# band.net
KiCad netlist of a schematic drawn in Altium Designer
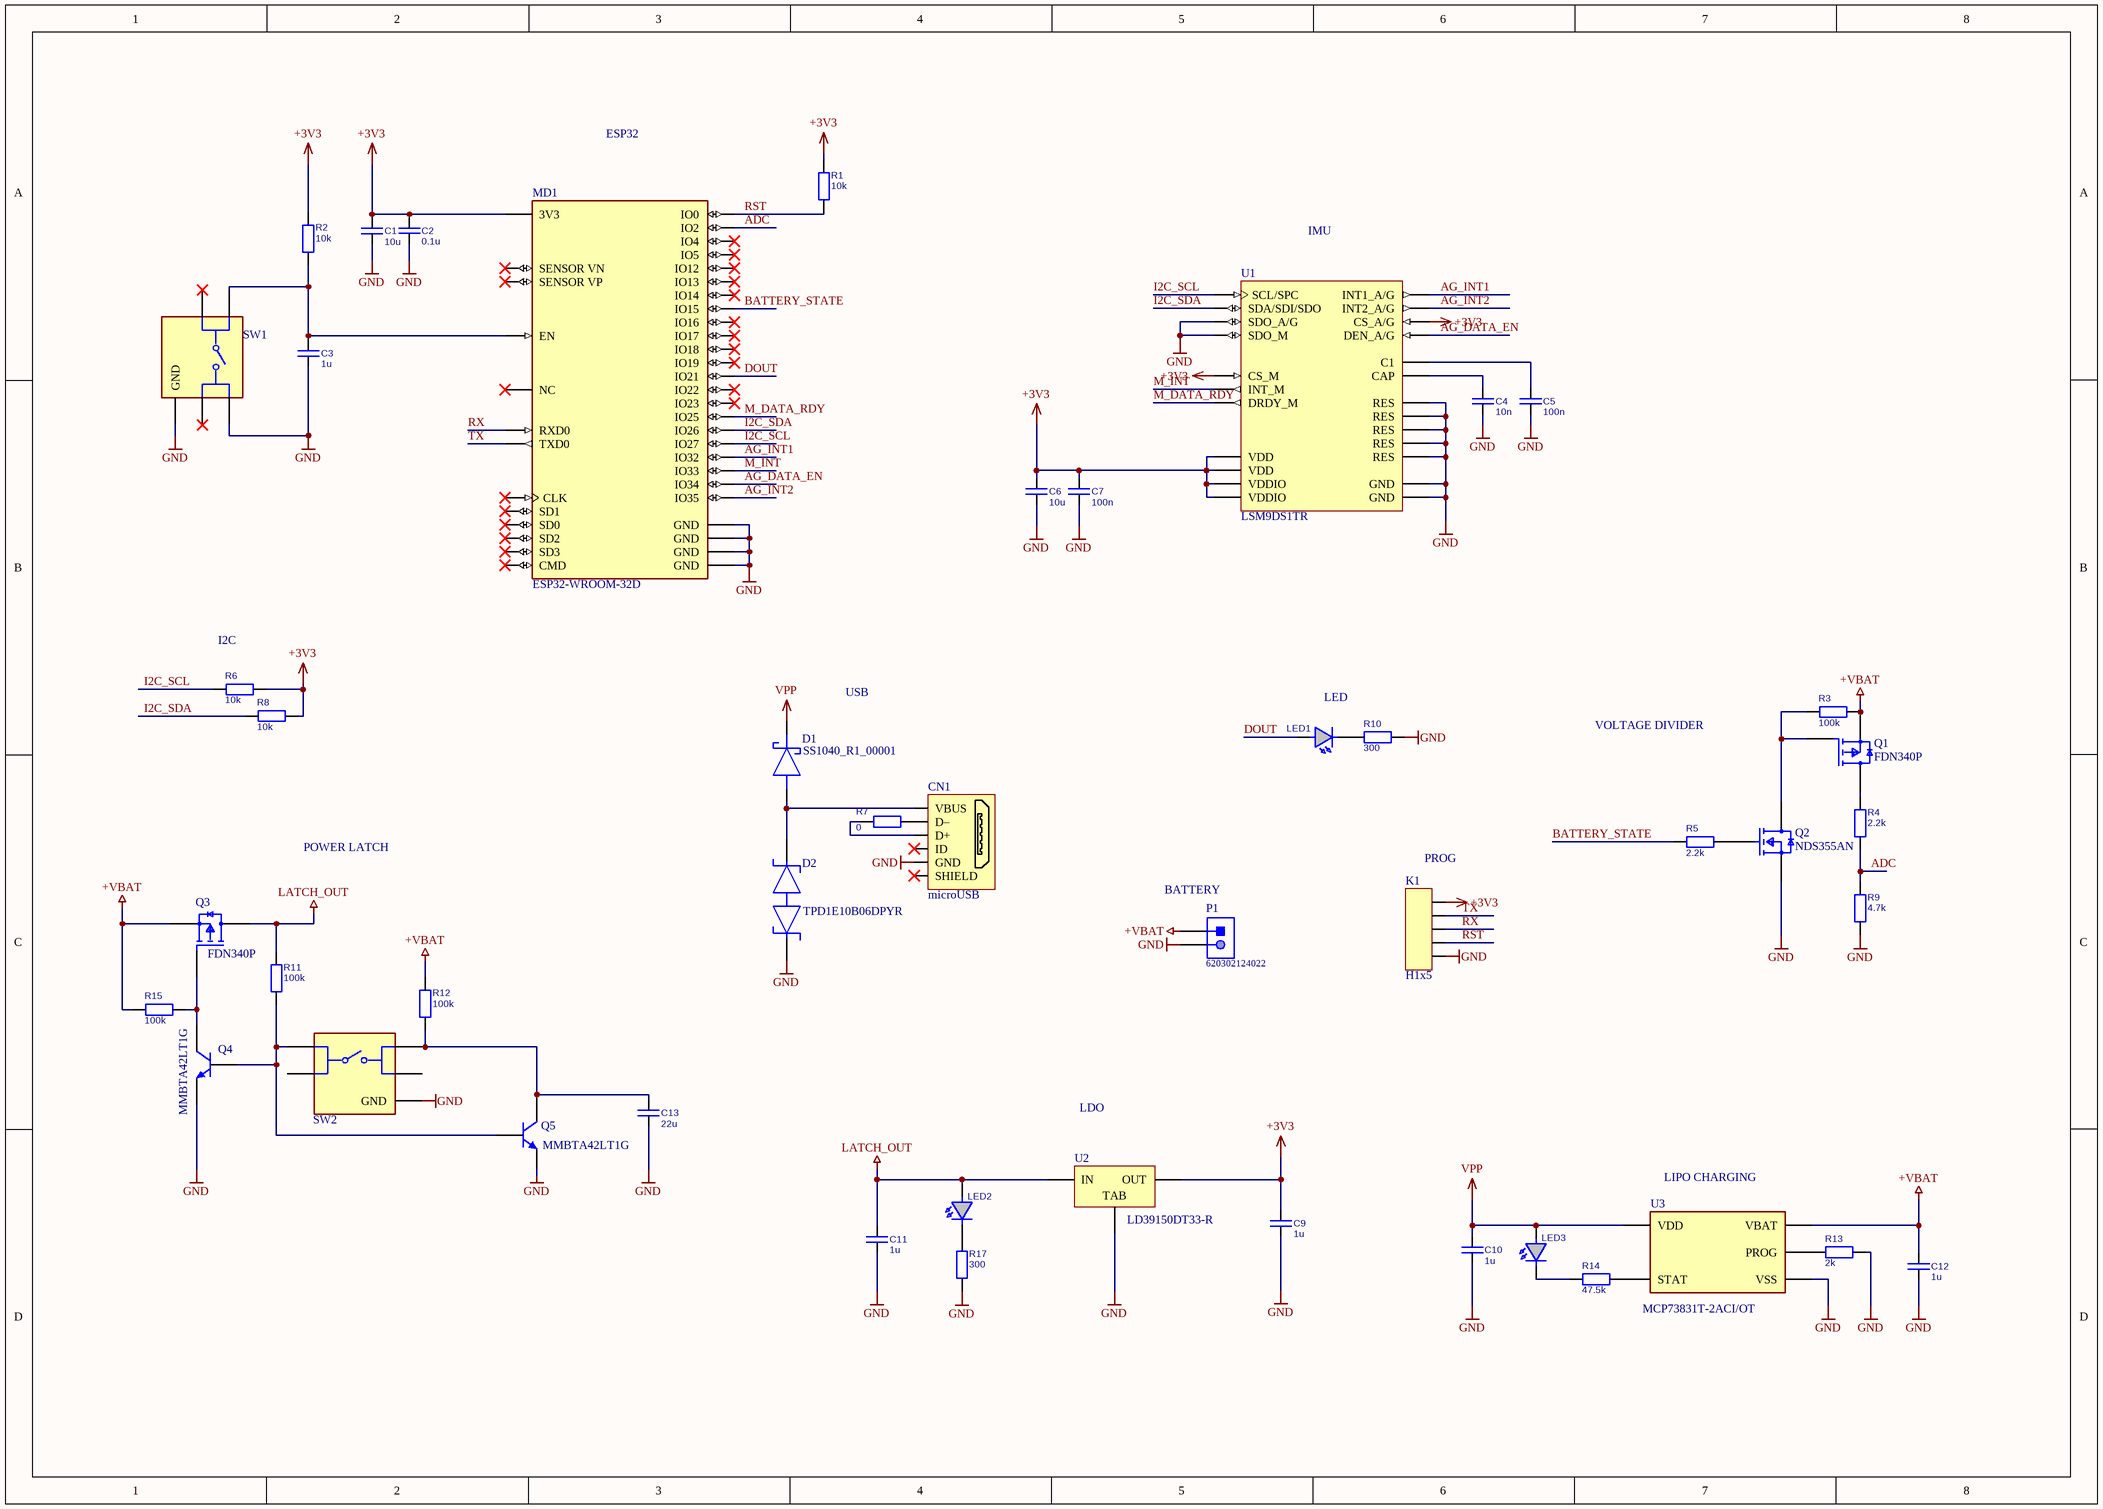
[diagram p0: band.SchDoc]

(export (version "E")
  (design (tool "Eeschema 10.0.6"))
  (components
    (comp (ref "C1")
      (value "10u")
      (footprint "C0805")
      (description "Capacitor")
      (libsource (lib "General") (part "C"))
    )
    (comp (ref "C2")
      (value "0.1u")
      (footprint "C0805")
      (description "Capacitor")
      (libsource (lib "General") (part "C"))
    )
    (comp (ref "C3")
      (value "1u")
      (footprint "C0805")
      (description "Capacitor")
      (libsource (lib "General") (part "C"))
    )
    (comp (ref "C4")
      (value "10n")
      (footprint "C0805")
      (description "Capacitor")
      (libsource (lib "General") (part "C"))
    )
    (comp (ref "C5")
      (value "100n")
      (footprint "C0805")
      (description "Capacitor")
      (libsource (lib "General") (part "C"))
    )
    (comp (ref "C6")
      (value "10u")
      (footprint "C0805")
      (description "Capacitor")
      (libsource (lib "General") (part "C"))
    )
    (comp (ref "C7")
      (value "100n")
      (footprint "C0805")
      (description "Capacitor")
      (libsource (lib "General") (part "C"))
    )
    (comp (ref "C9")
      (value "1u")
      (footprint "C0805")
      (description "Capacitor")
      (libsource (lib "General") (part "C"))
    )
    (comp (ref "C10")
      (value "1u")
      (footprint "C0805")
      (description "Capacitor")
      (libsource (lib "General") (part "C"))
    )
    (comp (ref "C11")
      (value "1u")
      (footprint "C0805")
      (description "Capacitor")
      (libsource (lib "General") (part "C"))
    )
    (comp (ref "C12")
      (value "1u")
      (footprint "C0805")
      (description "Capacitor")
      (libsource (lib "General") (part "C"))
    )
    (comp (ref "C13")
      (value "22u")
      (footprint "C0805")
      (description "Capacitor")
      (libsource (lib "General") (part "C"))
    )
    (comp (ref "CN1")
      (value "microUSB")
      (footprint "micro-USB-HRS-ZX62D-B-5PA8")
      (description "micro USB-B socket (HIROSE ZX62D-B-5PA8)")
      (libsource (lib "Kon_Tipk") (part "microUSB-B-socket (HIROSE ZX62D-B-5PA8)"))
    )
    (comp (ref "D1")
      (value "SS1040_R1_00001")
      (footprint "SamacSys:SS1040_R1_00001")
      (description "Schottky Diode")
      (libsource (lib "band") (part "SS1040_R1_00001"))
    )
    (comp (ref "D2")
      (value "TPD1E10B06DPYR")
      (footprint "FP-DPY0002A-MFG")
      (description "TVS DIODE 5.5V 14V 2X1SON")
      (libsource (lib "Altium Content Vault") (part "208e19b57522434895fa003e5d5b197"))
    )
    (comp (ref "K1")
      (value "H1x5")
      (footprint "H1x5")
      (description "Header 1x5 (male)")
      (libsource (lib "Kon_Tipk") (part "H1x5"))
    )
    (comp (ref "LED1") (value "LED") (footprint "LED0805G") (libsource (lib "Displays") (part "LED")))
    (comp (ref "LED2") (value "LED") (footprint "LED0805G") (libsource (lib "Displays") (part "LED")))
    (comp (ref "LED3") (value "LED") (footprint "LED0805G") (libsource (lib "Displays") (part "LED")))
    (comp (ref "MD1")
      (value "ESP32-WROOM-32D")
      (footprint "FP-ESP32-WROOM-32D-MFG")
      (description "WIFI MODULE 32MBITS SPI FLASH")
      (fields
        (field (name "OCTOPART") "https://octopart.com/esp32-wroom-32d-espressif+systems-91040050")
        (field (name "MANUFACTURER") "Espressif Systems")
      )
      (libsource (lib "Altium Content Vault") (part "a031a76f8c27026a7a7f4657ff233a3"))
    )
    (comp (ref "P1")
      (value "620302124022")
      (footprint "620302124022")
      (description "Male Shrouded Header WR-WTB, SMT, Vertical, pitch 2 mm, 1 x 2 position")
      (fields (field (name "MANUFACTURER") "Wurth Elektronik") (field (name "PUBLISHER") "WurthElektronik"))
      (libsource (lib "Altium Content Vault") (part "WE-CN-1P-M-R2"))
    )
    (comp (ref "Q1")
      (value "FDN340P")
      (footprint "FP-527AG-MFG")
      (description "MOSFET P-CH 20V 2A SSOT3")
      (libsource (lib "Altium Content Vault") (part "d23f43cc42f60b967b7caccf14518fd"))
    )
    (comp (ref "Q2")
      (value "NDS355AN")
      (footprint "FP-527AG-01-IPC_C")
      (description "MOSFET N-CH 30V 1.7A SSOT3")
      (fields
        (field (name "OCTOPART") "https://octopart.com/nds355an-on+semiconductor-84330922")
        (field (name "MANUFACTURER") "ON Semiconductor")
      )
      (libsource (lib "Altium Content Vault") (part "3b9c635fedb024a5347a57b145af9cc"))
    )
    (comp (ref "Q3")
      (value "FDN340P")
      (footprint "FP-527AG-MFG")
      (description "MOSFET P-CH 20V 2A SSOT3")
      (libsource (lib "Altium Content Vault") (part "d23f43cc42f60b967b7caccf14518fd"))
    )
    (comp (ref "Q4")
      (value "MMBTA42LT1G")
      (footprint "ONSC-SOT-23-3-318-08_V")
      (description "High Voltage Transistor, NPN Silicon, 3-Pin SOT-23, Pb-Free, Tape and Reel")
      (fields (field (name "MANUFACTURER") "On Semiconductor"))
      (libsource (lib "Altium Content Vault") (part "ONSC-NPN-B1E2C3-3"))
    )
    (comp (ref "Q5")
      (value "MMBTA42LT1G")
      (footprint "ONSC-SOT-23-3-318-08_V")
      (description "High Voltage Transistor, NPN Silicon, 3-Pin SOT-23, Pb-Free, Tape and Reel")
      (fields (field (name "MANUFACTURER") "On Semiconductor"))
      (libsource (lib "Altium Content Vault") (part "ONSC-NPN-B1E2C3-3"))
    )
    (comp (ref "R1")
      (value "10k")
      (footprint "R0805")
      (description "R")
      (libsource (lib "General") (part "R"))
    )
    (comp (ref "R2")
      (value "10k")
      (footprint "R0805")
      (description "R")
      (libsource (lib "General") (part "R"))
    )
    (comp (ref "R3")
      (value "100k")
      (footprint "R0805")
      (description "R")
      (libsource (lib "General") (part "R"))
    )
    (comp (ref "R4")
      (value "2.2k")
      (footprint "R0805")
      (description "R")
      (libsource (lib "General") (part "R"))
    )
    (comp (ref "R5")
      (value "2.2k")
      (footprint "R0805")
      (description "R")
      (libsource (lib "General") (part "R"))
    )
    (comp (ref "R6")
      (value "10k")
      (footprint "R0805")
      (description "R")
      (libsource (lib "General") (part "R"))
    )
    (comp (ref "R7") (value "0") (footprint "R0805") (description "R") (libsource (lib "General") (part "R")))
    (comp (ref "R8")
      (value "10k")
      (footprint "R0805")
      (description "R")
      (libsource (lib "General") (part "R"))
    )
    (comp (ref "R9")
      (value "4.7k")
      (footprint "R0805")
      (description "R")
      (libsource (lib "General") (part "R"))
    )
    (comp (ref "R10")
      (value "300")
      (footprint "R0805")
      (description "R")
      (libsource (lib "General") (part "R"))
    )
    (comp (ref "R11")
      (value "100k")
      (footprint "R0805")
      (description "R")
      (libsource (lib "General") (part "R"))
    )
    (comp (ref "R12")
      (value "100k")
      (footprint "R0805")
      (description "R")
      (libsource (lib "General") (part "R"))
    )
    (comp (ref "R13")
      (value "2k")
      (footprint "R0805")
      (description "R")
      (libsource (lib "General") (part "R"))
    )
    (comp (ref "R14")
      (value "47.5k")
      (footprint "R0805")
      (description "R")
      (libsource (lib "General") (part "R"))
    )
    (comp (ref "R15")
      (value "100k")
      (footprint "R0805")
      (description "R")
      (libsource (lib "General") (part "R"))
    )
    (comp (ref "R17")
      (value "300")
      (footprint "R0805")
      (description "R")
      (libsource (lib "General") (part "R"))
    )
    (comp (ref "SW1")
      (value "FSM1LP")
      (footprint "FP-FSM1LP-MFG")
      (description "SWITCH TACTILE SPST-NO 0.05A 24V")
      (libsource (lib "") (part "CMP-03402-000015-1_1"))
    )
    (comp (ref "SW2")
      (value "FSM1LP")
      (footprint "FP-FSM1LP-MFG")
      (description "SWITCH TACTILE SPST-NO 0.05A 24V")
      (libsource (lib "band") (part "CMP-03402-000015-1"))
    )
    (comp (ref "U1")
      (value "LSM9DS1TR")
      (footprint "STM-LGA-24_3500X3000X1000")
      (fields (field (name "PARTNUMBER") "LSM9DS1") (field (name "MANUFACTURER") "STMicroelectronics"))
      (libsource (lib "Altium Content Vault") (part "STM-LSM9DS1-24"))
    )
    (comp (ref "U2")
      (value "LD39150DT33-R")
      (footprint "TO-252_M")
      (description "Ultra Low Drop BICMOS Voltage Regulator, 3.3V, 3-Pin DPAK, Tape and Reel")
      (libsource (lib "Altium Content Vault") (part "PM-REG-LD29150-SOT3"))
    )
    (comp (ref "U3")
      (value "MCP73831T-2ACI/OT")
      (footprint "FP-C04-091-OT-IPC_B")
      (description "IC CONTROLLR LI-ION 4.2V SOT23-5")
      (libsource (lib "Altium Content Vault") (part "61f5a3bb3429d9e0caadea342aa3b19"))
    )
  )
  (nets
    (net (code "1") (name "+3V3") (class "Default")
      (node (ref "C1") (pin "1") (pinfunction "1_1") (pintype "passive"))
      (node (ref "C2") (pin "1") (pinfunction "1_1") (pintype "passive"))
      (node (ref "C6") (pin "1") (pinfunction "1_1") (pintype "passive"))
      (node (ref "C7") (pin "1") (pinfunction "1_1") (pintype "passive"))
      (node (ref "C9") (pin "1") (pinfunction "1_1") (pintype "passive"))
      (node (ref "K1") (pin "1") (pinfunction "1_1") (pintype "passive"))
      (node (ref "MD1") (pin "2") (pinfunction "3V3_2") (pintype "power_in"))
      (node (ref "R1") (pin "1") (pintype "passive"))
      (node (ref "R2") (pin "2") (pintype "passive"))
      (node (ref "R6") (pin "2") (pintype "passive"))
      (node (ref "R8") (pin "2") (pintype "passive"))
      (node (ref "U1") (pin "1") (pinfunction "VDDIO_1") (pintype "power_in"))
      (node (ref "U1") (pin "22") (pinfunction "VDD_22") (pintype "power_in"))
      (node (ref "U1") (pin "23") (pinfunction "VDD_23") (pintype "power_in"))
      (node (ref "U1") (pin "3") (pinfunction "VDDIO_3") (pintype "power_in"))
      (node (ref "U1") (pin "7") (pinfunction "CS_A/G_7") (pintype "input"))
      (node (ref "U1") (pin "8") (pinfunction "CS_M_8") (pintype "input"))
      (node (ref "U2") (pin "3") (pinfunction "OUT_3") (pintype "power_in"))
    )
    (net (code "2") (name "+VBAT") (class "Default")
      (node (ref "C12") (pin "1") (pinfunction "1_1") (pintype "passive"))
      (node (ref "P1") (pin "1") (pinfunction "1_1") (pintype "passive"))
      (node (ref "Q1") (pin "2") (pinfunction "S_2") (pintype "passive"))
      (node (ref "Q3") (pin "2") (pinfunction "S_2") (pintype "passive"))
      (node (ref "R12") (pin "2") (pintype "passive"))
      (node (ref "R15") (pin "2") (pintype "passive"))
      (node (ref "R3") (pin "1") (pintype "passive"))
      (node (ref "U3") (pin "3") (pinfunction "VBAT_3") (pintype "power_in"))
    )
    (net (code "3") (name "/ADC") (class "Default")
      (node (ref "MD1") (pin "24") (pinfunction "IO2_24") (pintype "bidirectional"))
      (node (ref "R4") (pin "2") (pintype "passive"))
      (node (ref "R9") (pin "2") (pintype "passive"))
    )
    (net (code "4") (name "/AG_DATA_EN") (class "Default")
      (node (ref "MD1") (pin "6") (pinfunction "IO34_6") (pintype "bidirectional"))
      (node (ref "U1") (pin "13") (pinfunction "DEN_A/G_13") (pintype "input"))
    )
    (net (code "5") (name "/AG_INT1") (class "Default")
      (node (ref "MD1") (pin "8") (pinfunction "IO32_8") (pintype "bidirectional"))
      (node (ref "U1") (pin "11") (pinfunction "INT1_A/G_11") (pintype "output"))
    )
    (net (code "6") (name "/AG_INT2") (class "Default")
      (node (ref "MD1") (pin "7") (pinfunction "IO35_7") (pintype "bidirectional"))
      (node (ref "U1") (pin "12") (pinfunction "INT2_A/G_12") (pintype "output"))
    )
    (net (code "7") (name "/BATTERY_STATE") (class "Default")
      (node (ref "MD1") (pin "23") (pinfunction "IO15_23") (pintype "bidirectional"))
      (node (ref "R5") (pin "1") (pintype "passive"))
    )
    (net (code "8") (name "/DOUT") (class "Default")
      (node (ref "LED1") (pin "A") (pinfunction "1_A") (pintype "passive"))
      (node (ref "MD1") (pin "33") (pinfunction "IO21_33") (pintype "bidirectional"))
    )
    (net (code "9") (name "/I2C_SCL") (class "Default")
      (node (ref "MD1") (pin "12") (pinfunction "IO27_12") (pintype "bidirectional"))
      (node (ref "R6") (pin "1") (pintype "passive"))
      (node (ref "U1") (pin "2") (pinfunction "SCL/SPC_2") (pintype "input"))
    )
    (net (code "10") (name "/I2C_SDA") (class "Default")
      (node (ref "MD1") (pin "11") (pinfunction "IO26_11") (pintype "bidirectional"))
      (node (ref "R8") (pin "1") (pintype "passive"))
      (node (ref "U1") (pin "4") (pinfunction "SDA/SDI/SDO_4") (pintype "bidirectional"))
    )
    (net (code "11") (name "/M_DATA_RDY") (class "Default")
      (node (ref "MD1") (pin "10") (pinfunction "IO25_10") (pintype "bidirectional"))
      (node (ref "U1") (pin "9") (pinfunction "DRDY_M_9") (pintype "output"))
    )
    (net (code "12") (name "/M_INT") (class "Default")
      (node (ref "MD1") (pin "9") (pinfunction "IO33_9") (pintype "bidirectional"))
      (node (ref "U1") (pin "10") (pinfunction "INT_M_10") (pintype "output"))
    )
    (net (code "13") (name "/RST") (class "Default")
      (node (ref "K1") (pin "4") (pinfunction "4_4") (pintype "passive"))
      (node (ref "MD1") (pin "25") (pinfunction "IO0_25") (pintype "bidirectional"))
      (node (ref "R1") (pin "2") (pintype "passive"))
    )
    (net (code "14") (name "/RX") (class "Default")
      (node (ref "K1") (pin "3") (pinfunction "3_3") (pintype "passive"))
      (node (ref "MD1") (pin "34") (pinfunction "RXD0_34") (pintype "input"))
    )
    (net (code "15") (name "/TX") (class "Default")
      (node (ref "K1") (pin "2") (pinfunction "2_2") (pintype "passive"))
      (node (ref "MD1") (pin "35") (pinfunction "TXD0_35") (pintype "output"))
    )
    (net (code "16") (name "GND") (class "Default")
      (node (ref "C1") (pin "2") (pinfunction "2_2") (pintype "passive"))
      (node (ref "C10") (pin "2") (pinfunction "2_2") (pintype "passive"))
      (node (ref "C11") (pin "1") (pinfunction "1_1") (pintype "passive"))
      (node (ref "C12") (pin "2") (pinfunction "2_2") (pintype "passive"))
      (node (ref "C13") (pin "1") (pinfunction "1_1") (pintype "passive"))
      (node (ref "C2") (pin "2") (pinfunction "2_2") (pintype "passive"))
      (node (ref "C3") (pin "2") (pinfunction "2_2") (pintype "passive"))
      (node (ref "C4") (pin "2") (pinfunction "2_2") (pintype "passive"))
      (node (ref "C5") (pin "2") (pinfunction "2_2") (pintype "passive"))
      (node (ref "C6") (pin "2") (pinfunction "2_2") (pintype "passive"))
      (node (ref "C7") (pin "2") (pinfunction "2_2") (pintype "passive"))
      (node (ref "C9") (pin "2") (pinfunction "2_2") (pintype "passive"))
      (node (ref "CN1") (pin "5") (pinfunction "GND_5") (pintype "passive"))
      (node (ref "D2") (pin "1") (pinfunction "1_1") (pintype "passive"))
      (node (ref "K1") (pin "5") (pinfunction "5_5") (pintype "passive"))
      (node (ref "MD1") (pin "1") (pinfunction "GND_1") (pintype "power_in"))
      (node (ref "MD1") (pin "15") (pinfunction "GND_15") (pintype "power_in"))
      (node (ref "MD1") (pin "38") (pinfunction "GND_38") (pintype "power_in"))
      (node (ref "MD1") (pin "39") (pinfunction "GND_39") (pintype "power_in"))
      (node (ref "P1") (pin "2") (pinfunction "2_2") (pintype "passive"))
      (node (ref "Q2") (pin "2") (pinfunction "S_2") (pintype "passive"))
      (node (ref "Q4") (pin "2") (pinfunction "E_2") (pintype "passive"))
      (node (ref "Q5") (pin "2") (pinfunction "E_2") (pintype "passive"))
      (node (ref "R10") (pin "2") (pintype "passive"))
      (node (ref "R13") (pin "1") (pintype "passive"))
      (node (ref "R17") (pin "1") (pintype "passive"))
      (node (ref "R9") (pin "1") (pintype "passive"))
      (node (ref "SW1") (pin "3") (pinfunction "3_3") (pintype "passive"))
      (node (ref "SW1") (pin "5") (pinfunction "GND_5") (pintype "power_in"))
      (node (ref "SW2") (pin "5") (pinfunction "GND_5") (pintype "power_in"))
      (node (ref "U1") (pin "14") (pinfunction "RES_14") (pintype "passive"))
      (node (ref "U1") (pin "15") (pinfunction "RES_15") (pintype "passive"))
      (node (ref "U1") (pin "16") (pinfunction "RES_16") (pintype "passive"))
      (node (ref "U1") (pin "17") (pinfunction "RES_17") (pintype "passive"))
      (node (ref "U1") (pin "18") (pinfunction "RES_18") (pintype "passive"))
      (node (ref "U1") (pin "19") (pinfunction "GND_19") (pintype "power_in"))
      (node (ref "U1") (pin "20") (pinfunction "GND_20") (pintype "power_in"))
      (node (ref "U1") (pin "5") (pinfunction "SDO_A/G_5") (pintype "bidirectional"))
      (node (ref "U1") (pin "6") (pinfunction "SDO_M_6") (pintype "bidirectional"))
      (node (ref "U2") (pin "4") (pinfunction "TAB_4") (pintype "passive"))
      (node (ref "U3") (pin "2") (pinfunction "VSS_2") (pintype "power_in"))
    )
    (net (code "17") (name "LATCH_OUT") (class "Default")
      (node (ref "C11") (pin "2") (pinfunction "2_2") (pintype "passive"))
      (node (ref "LED2") (pin "A") (pinfunction "1_A") (pintype "passive"))
      (node (ref "Q3") (pin "3") (pinfunction "D_3") (pintype "passive"))
      (node (ref "R11") (pin "2") (pintype "passive"))
      (node (ref "U2") (pin "1") (pinfunction "IN_1") (pintype "power_in"))
    )
    (net (code "18") (name "Net-(CN1-D+)") (class "Default")
      (node (ref "CN1") (pin "3") (pinfunction "D+_3") (pintype "passive"))
      (node (ref "R7") (pin "2") (pintype "passive"))
    )
    (net (code "19") (name "Net-(CN1-D–)") (class "Default")
      (node (ref "CN1") (pin "2") (pinfunction "D–_2") (pintype "passive"))
      (node (ref "R7") (pin "1") (pintype "passive"))
    )
    (net (code "20") (name "Net-(CN1-VBUS)") (class "Default")
      (node (ref "CN1") (pin "1") (pinfunction "VBUS_1") (pintype "passive"))
      (node (ref "D1") (pin "2") (pinfunction "A_2") (pintype "passive"))
      (node (ref "D2") (pin "2") (pinfunction "2_2") (pintype "passive"))
    )
    (net (code "21") (name "Net-(LED1-2)") (class "Default")
      (node (ref "LED1") (pin "K") (pinfunction "2_K") (pintype "passive"))
      (node (ref "R10") (pin "1") (pintype "passive"))
    )
    (net (code "22") (name "Net-(LED2-2)") (class "Default")
      (node (ref "LED2") (pin "K") (pinfunction "2_K") (pintype "passive"))
      (node (ref "R17") (pin "2") (pintype "passive"))
    )
    (net (code "23") (name "Net-(LED3-2)") (class "Default")
      (node (ref "LED3") (pin "K") (pinfunction "2_K") (pintype "passive"))
      (node (ref "R14") (pin "2") (pintype "passive"))
    )
    (net (code "24") (name "Net-(MD1-EN)") (class "Default")
      (node (ref "C3") (pin "1") (pinfunction "1_1") (pintype "passive"))
      (node (ref "MD1") (pin "3") (pinfunction "EN_3") (pintype "input"))
      (node (ref "R2") (pin "1") (pintype "passive"))
      (node (ref "SW1") (pin "1") (pinfunction "1_1") (pintype "passive"))
    )
    (net (code "25") (name "Net-(Q1-D)") (class "Default")
      (node (ref "Q1") (pin "3") (pinfunction "D_3") (pintype "passive"))
      (node (ref "R4") (pin "1") (pintype "passive"))
    )
    (net (code "26") (name "Net-(Q1-G)") (class "Default")
      (node (ref "Q1") (pin "1") (pinfunction "G_1") (pintype "passive"))
      (node (ref "Q2") (pin "3") (pinfunction "D_3") (pintype "passive"))
      (node (ref "R3") (pin "2") (pintype "passive"))
    )
    (net (code "27") (name "Net-(Q2-G)") (class "Default")
      (node (ref "Q2") (pin "1") (pinfunction "G_1") (pintype "passive"))
      (node (ref "R5") (pin "2") (pintype "passive"))
    )
    (net (code "28") (name "Net-(Q3-G)") (class "Default")
      (node (ref "Q3") (pin "1") (pinfunction "G_1") (pintype "passive"))
      (node (ref "Q4") (pin "3") (pinfunction "C_3") (pintype "passive"))
      (node (ref "R15") (pin "1") (pintype "passive"))
    )
    (net (code "29") (name "Net-(Q4-B)") (class "Default")
      (node (ref "Q4") (pin "1") (pinfunction "B_1") (pintype "passive"))
      (node (ref "Q5") (pin "1") (pinfunction "B_1") (pintype "passive"))
      (node (ref "R11") (pin "1") (pintype "passive"))
      (node (ref "SW2") (pin "1") (pinfunction "1_1") (pintype "passive"))
    )
    (net (code "30") (name "Net-(Q5-C)") (class "Default")
      (node (ref "C13") (pin "2") (pinfunction "2_2") (pintype "passive"))
      (node (ref "Q5") (pin "3") (pinfunction "C_3") (pintype "passive"))
      (node (ref "R12") (pin "1") (pintype "passive"))
      (node (ref "SW2") (pin "3") (pinfunction "3_3") (pintype "passive"))
    )
    (net (code "31") (name "Net-(U1-C1)") (class "Default")
      (node (ref "C5") (pin "1") (pinfunction "1_1") (pintype "passive"))
      (node (ref "U1") (pin "24") (pinfunction "C1_24") (pintype "passive"))
    )
    (net (code "32") (name "Net-(U1-CAP)") (class "Default")
      (node (ref "C4") (pin "1") (pinfunction "1_1") (pintype "passive"))
      (node (ref "U1") (pin "21") (pinfunction "CAP_21") (pintype "passive"))
    )
    (net (code "33") (name "Net-(U3-PROG)") (class "Default")
      (node (ref "R13") (pin "2") (pintype "passive"))
      (node (ref "U3") (pin "5") (pinfunction "PROG_5") (pintype "passive"))
    )
    (net (code "34") (name "Net-(U3-STAT)") (class "Default")
      (node (ref "R14") (pin "1") (pintype "passive"))
      (node (ref "U3") (pin "1") (pinfunction "STAT_1") (pintype "passive"))
    )
    (net (code "35") (name "VPP") (class "Default")
      (node (ref "C10") (pin "1") (pinfunction "1_1") (pintype "passive"))
      (node (ref "D1") (pin "1") (pinfunction "K_1") (pintype "passive"))
      (node (ref "LED3") (pin "A") (pinfunction "1_A") (pintype "passive"))
      (node (ref "U3") (pin "4") (pinfunction "VDD_4") (pintype "power_in"))
    )
    (net (code "36") (name "unconnected-(CN1-ID-Pad4)") (class "Default")
      (node (ref "CN1") (pin "4") (pinfunction "ID_4") (pintype "passive+no_connect"))
    )
    (net (code "37") (name "unconnected-(CN1-SHIELD-Pad6)") (class "Default")
      (node (ref "CN1") (pin "6") (pinfunction "SHIELD_6") (pintype "passive+no_connect"))
    )
    (net (code "38") (name "unconnected-(MD1-CLK-Pad20)") (class "Default")
      (node (ref "MD1") (pin "20") (pinfunction "CLK_20") (pintype "input+no_connect"))
    )
    (net (code "39") (name "unconnected-(MD1-CMD-Pad19)") (class "Default")
      (node (ref "MD1") (pin "19") (pinfunction "CMD_19") (pintype "bidirectional+no_connect"))
    )
    (net (code "40") (name "unconnected-(MD1-IO4-Pad26)") (class "Default")
      (node (ref "MD1") (pin "26") (pinfunction "IO4_26") (pintype "bidirectional+no_connect"))
    )
    (net (code "41") (name "unconnected-(MD1-IO5-Pad29)") (class "Default")
      (node (ref "MD1") (pin "29") (pinfunction "IO5_29") (pintype "bidirectional+no_connect"))
    )
    (net (code "42") (name "unconnected-(MD1-IO12-Pad14)") (class "Default")
      (node (ref "MD1") (pin "14") (pinfunction "IO12_14") (pintype "bidirectional+no_connect"))
    )
    (net (code "43") (name "unconnected-(MD1-IO13-Pad16)") (class "Default")
      (node (ref "MD1") (pin "16") (pinfunction "IO13_16") (pintype "bidirectional+no_connect"))
    )
    (net (code "44") (name "unconnected-(MD1-IO14-Pad13)") (class "Default")
      (node (ref "MD1") (pin "13") (pinfunction "IO14_13") (pintype "bidirectional+no_connect"))
    )
    (net (code "45") (name "unconnected-(MD1-IO16-Pad27)") (class "Default")
      (node (ref "MD1") (pin "27") (pinfunction "IO16_27") (pintype "bidirectional+no_connect"))
    )
    (net (code "46") (name "unconnected-(MD1-IO17-Pad28)") (class "Default")
      (node (ref "MD1") (pin "28") (pinfunction "IO17_28") (pintype "bidirectional+no_connect"))
    )
    (net (code "47") (name "unconnected-(MD1-IO18-Pad30)") (class "Default")
      (node (ref "MD1") (pin "30") (pinfunction "IO18_30") (pintype "bidirectional+no_connect"))
    )
    (net (code "48") (name "unconnected-(MD1-IO19-Pad31)") (class "Default")
      (node (ref "MD1") (pin "31") (pinfunction "IO19_31") (pintype "bidirectional+no_connect"))
    )
    (net (code "49") (name "unconnected-(MD1-IO22-Pad36)") (class "Default")
      (node (ref "MD1") (pin "36") (pinfunction "IO22_36") (pintype "bidirectional+no_connect"))
    )
    (net (code "50") (name "unconnected-(MD1-IO23-Pad37)") (class "Default")
      (node (ref "MD1") (pin "37") (pinfunction "IO23_37") (pintype "bidirectional+no_connect"))
    )
    (net (code "51") (name "unconnected-(MD1-NC-Pad32)") (class "Default")
      (node (ref "MD1") (pin "32") (pinfunction "NC_32") (pintype "passive+no_connect"))
    )
    (net (code "52") (name "unconnected-(MD1-SD0-Pad21)") (class "Default")
      (node (ref "MD1") (pin "21") (pinfunction "SD0_21") (pintype "bidirectional+no_connect"))
    )
    (net (code "53") (name "unconnected-(MD1-SD1-Pad22)") (class "Default")
      (node (ref "MD1") (pin "22") (pinfunction "SD1_22") (pintype "bidirectional+no_connect"))
    )
    (net (code "54") (name "unconnected-(MD1-SD2-Pad17)") (class "Default")
      (node (ref "MD1") (pin "17") (pinfunction "SD2_17") (pintype "bidirectional+no_connect"))
    )
    (net (code "55") (name "unconnected-(MD1-SD3-Pad18)") (class "Default")
      (node (ref "MD1") (pin "18") (pinfunction "SD3_18") (pintype "bidirectional+no_connect"))
    )
    (net (code "56") (name "unconnected-(MD1-SENSOR_VN-Pad5)") (class "Default")
      (node (ref "MD1") (pin "5") (pinfunction "SENSOR_VN_5") (pintype "bidirectional+no_connect"))
    )
    (net (code "57") (name "unconnected-(MD1-SENSOR_VP-Pad4)") (class "Default")
      (node (ref "MD1") (pin "4") (pinfunction "SENSOR_VP_4") (pintype "bidirectional+no_connect"))
    )
    (net (code "58") (name "unconnected-(SW1-Pad2)") (class "Default")
      (node (ref "SW1") (pin "2") (pinfunction "2_2") (pintype "passive+no_connect"))
    )
    (net (code "59") (name "unconnected-(SW1-Pad4)") (class "Default")
      (node (ref "SW1") (pin "4") (pinfunction "4_4") (pintype "passive+no_connect"))
    )
    (net (code "60") (name "unconnected-(SW2-Pad2)") (class "Default")
      (node (ref "SW2") (pin "2") (pinfunction "2_2") (pintype "passive"))
    )
    (net (code "61") (name "unconnected-(SW2-Pad4)") (class "Default")
      (node (ref "SW2") (pin "4") (pinfunction "4_4") (pintype "passive"))
    )
  )
)
